# ARTIC_R2.net
KiCad netlist of a schematic drawn in EAGLE
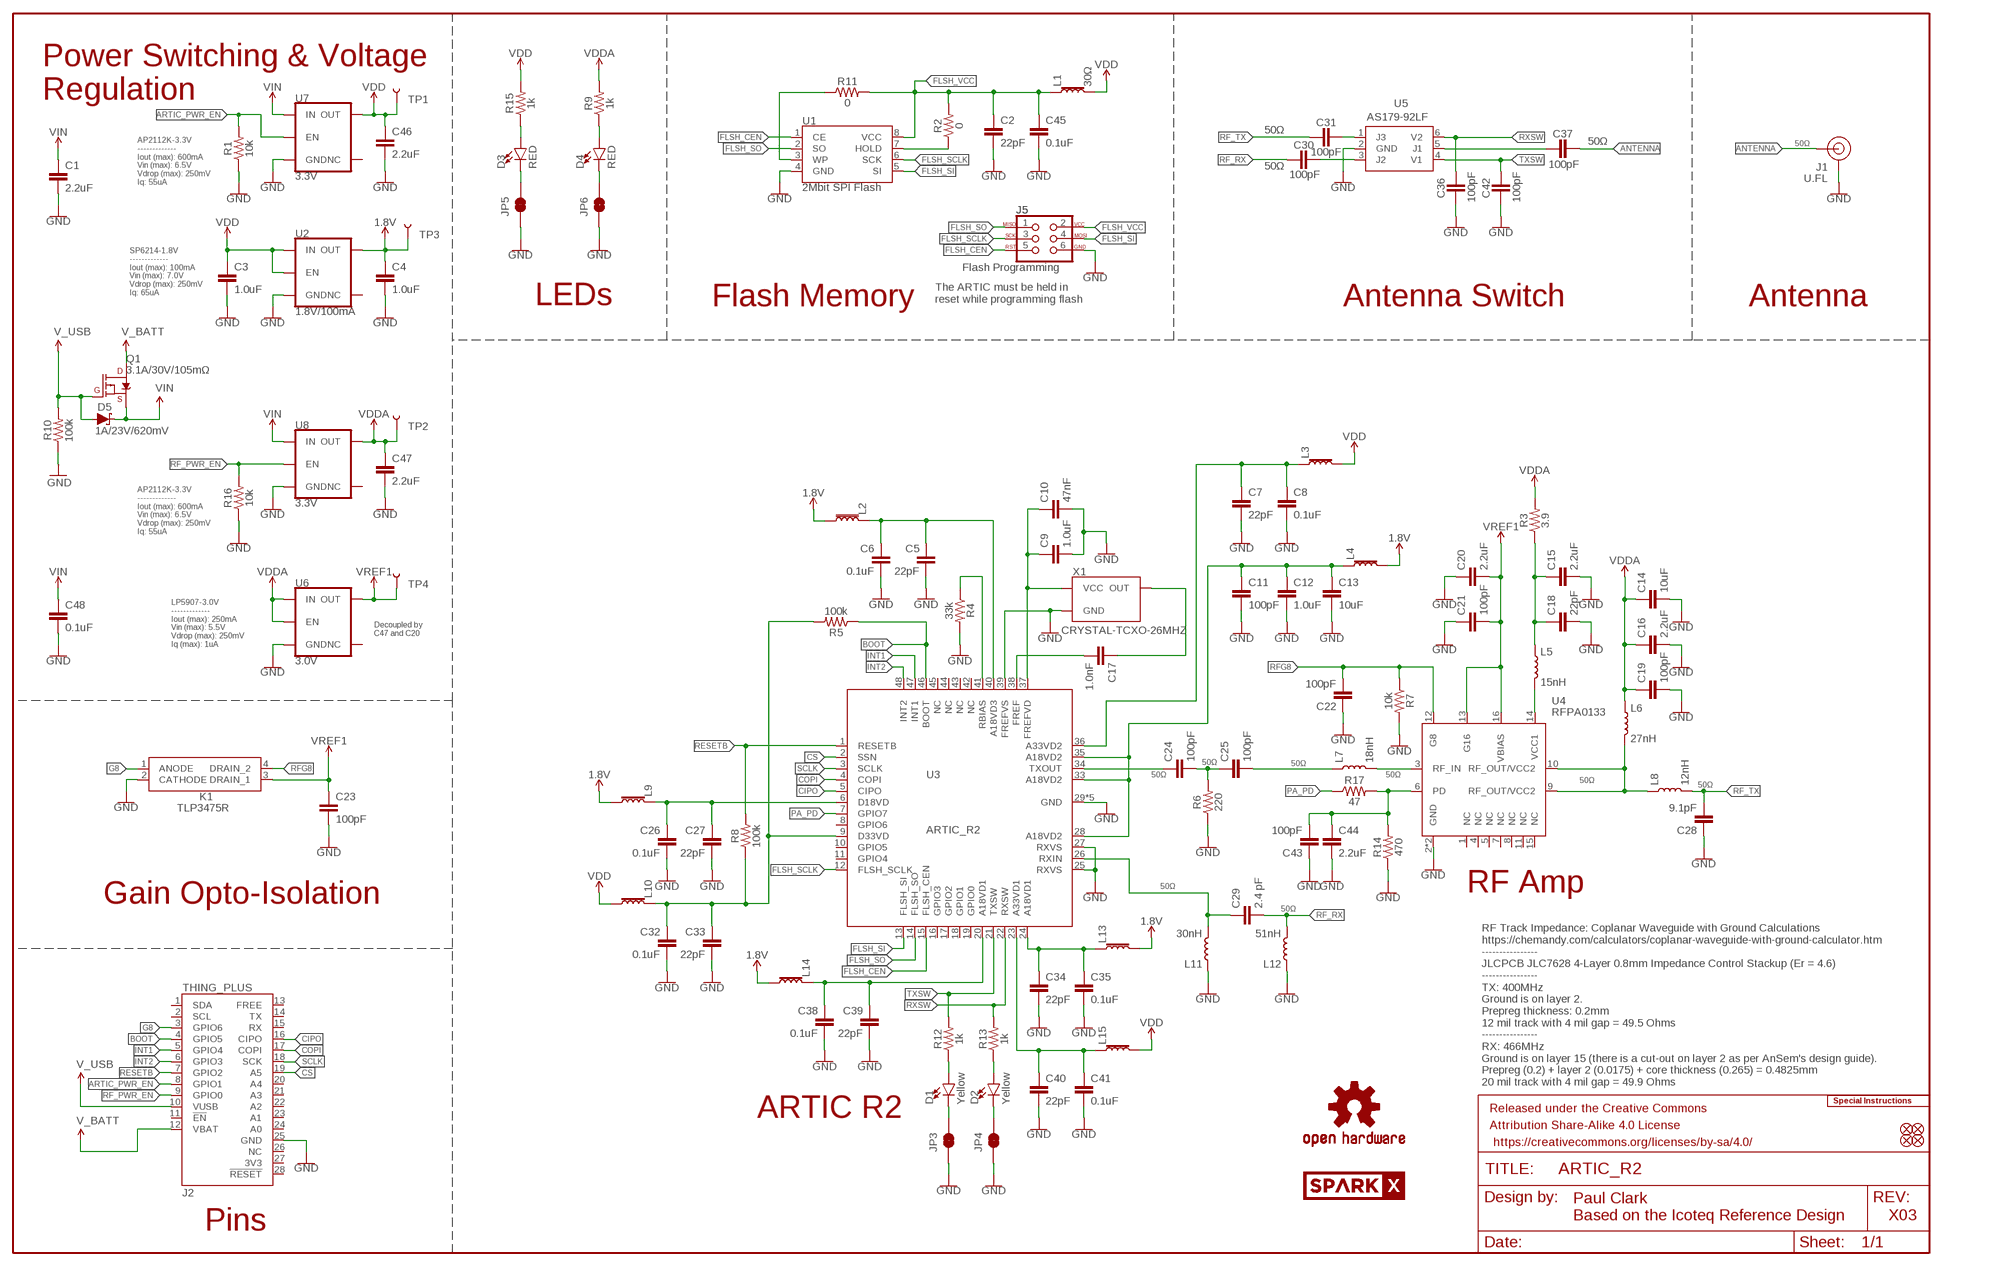
[diagram p0: schematic, sheet 1]

(export (version "E")
  (design (tool "Eeschema 10.0.6"))
  (components
    (comp (ref "C1")
      (value "2.2uF")
      (footprint "eagle-import:0402-TIGHT")
      (libsource (lib "eagle-import") (part "2.2UF-0402_TIGHT-10V-10%-X5R"))
    )
    (comp (ref "C2")
      (value "22pF")
      (footprint "eagle-import:0402-TIGHT")
      (libsource (lib "eagle-import") (part "22PF-0402T-16V-10%"))
    )
    (comp (ref "C3")
      (value "1.0uF")
      (footprint "eagle-import:0402-TIGHT")
      (libsource (lib "eagle-import") (part "1.0UF-0402T-16V-10%"))
    )
    (comp (ref "C4")
      (value "1.0uF")
      (footprint "eagle-import:0402-TIGHT")
      (libsource (lib "eagle-import") (part "1.0UF-0402T-16V-10%"))
    )
    (comp (ref "C5")
      (value "22pF")
      (footprint "eagle-import:0402-TIGHT")
      (libsource (lib "eagle-import") (part "22PF-0402T-16V-10%"))
    )
    (comp (ref "C6")
      (value "0.1uF")
      (footprint "eagle-import:0402-TIGHT")
      (libsource (lib "eagle-import") (part "0.1UF-0402T-6.3V-10%-X7R"))
    )
    (comp (ref "C7")
      (value "22pF")
      (footprint "eagle-import:0402-TIGHT")
      (libsource (lib "eagle-import") (part "22PF-0402T-16V-10%"))
    )
    (comp (ref "C8")
      (value "0.1uF")
      (footprint "eagle-import:0402-TIGHT")
      (libsource (lib "eagle-import") (part "0.1UF-0402T-6.3V-10%-X7R"))
    )
    (comp (ref "C9")
      (value "1.0uF")
      (footprint "eagle-import:0402-TIGHT")
      (libsource (lib "eagle-import") (part "1.0UF-0402T-16V-10%"))
    )
    (comp (ref "C10")
      (value "47nF")
      (footprint "eagle-import:0402-TIGHT")
      (libsource (lib "eagle-import") (part "47NF-0402_TIGHT-25V-10%-X7R"))
    )
    (comp (ref "C11")
      (value "100pF")
      (footprint "eagle-import:0402-TIGHT")
      (libsource (lib "eagle-import") (part "100PF-0402T-50V-5%"))
    )
    (comp (ref "C12")
      (value "1.0uF")
      (footprint "eagle-import:0402-TIGHT")
      (libsource (lib "eagle-import") (part "1.0UF-0402T-16V-10%"))
    )
    (comp (ref "C13")
      (value "10uF")
      (footprint "eagle-import:0402-TIGHT")
      (libsource (lib "eagle-import") (part "10UF-0402T-6.3V-20%"))
    )
    (comp (ref "C14")
      (value "10uF")
      (footprint "eagle-import:0402-TIGHT")
      (libsource (lib "eagle-import") (part "10UF-0402T-6.3V-20%"))
    )
    (comp (ref "C15")
      (value "2.2uF")
      (footprint "eagle-import:0402-TIGHT")
      (libsource (lib "eagle-import") (part "2.2UF-0402_TIGHT-10V-10%-X5R"))
    )
    (comp (ref "C16")
      (value "2.2uF")
      (footprint "eagle-import:0402-TIGHT")
      (libsource (lib "eagle-import") (part "2.2UF-0402_TIGHT-10V-10%-X5R"))
    )
    (comp (ref "C17")
      (value "1.0nF")
      (footprint "eagle-import:0402-TIGHT")
      (libsource (lib "eagle-import") (part "1.0NF/1000PF-0402_TIGHT-50V-10%"))
    )
    (comp (ref "C18")
      (value "22pF")
      (footprint "eagle-import:0402-TIGHT")
      (libsource (lib "eagle-import") (part "22PF-0402T-16V-10%"))
    )
    (comp (ref "C19")
      (value "100pF")
      (footprint "eagle-import:0402-TIGHT")
      (libsource (lib "eagle-import") (part "100PF-0402T-50V-5%"))
    )
    (comp (ref "C20")
      (value "2.2uF")
      (footprint "eagle-import:0402-TIGHT")
      (libsource (lib "eagle-import") (part "2.2UF-0402_TIGHT-10V-10%-X5R"))
    )
    (comp (ref "C21")
      (value "100pF")
      (footprint "eagle-import:0402-TIGHT")
      (libsource (lib "eagle-import") (part "100PF-0402T-50V-5%"))
    )
    (comp (ref "C22")
      (value "100pF")
      (footprint "eagle-import:0402-TIGHT")
      (libsource (lib "eagle-import") (part "100PF-0402T-50V-5%"))
    )
    (comp (ref "C23")
      (value "100pF")
      (footprint "eagle-import:0402-TIGHT")
      (libsource (lib "eagle-import") (part "100PF-0402T-50V-5%"))
    )
    (comp (ref "C24")
      (value "100pF")
      (footprint "eagle-import:0402-TIGHT")
      (libsource (lib "eagle-import") (part "100PF-0402T-50V-5%"))
    )
    (comp (ref "C25")
      (value "100pF")
      (footprint "eagle-import:0402-TIGHT")
      (libsource (lib "eagle-import") (part "100PF-0402T-50V-5%"))
    )
    (comp (ref "C26")
      (value "0.1uF")
      (footprint "eagle-import:0402-TIGHT")
      (libsource (lib "eagle-import") (part "0.1UF-0402T-6.3V-10%-X7R"))
    )
    (comp (ref "C27")
      (value "22pF")
      (footprint "eagle-import:0402-TIGHT")
      (libsource (lib "eagle-import") (part "22PF-0402T-16V-10%"))
    )
    (comp (ref "C28")
      (value "9.1pF")
      (footprint "eagle-import:0402-TIGHT")
      (fields (field (name "MOUSER_PART") "609-500R07S9R1CV4T"))
      (libsource (lib "eagle-import") (part "9.1PF-0402-TIGHT"))
    )
    (comp (ref "C29")
      (value "2.4 pF")
      (footprint "eagle-import:0402_MURATA")
      (libsource (lib "eagle-import") (part "2.4PF-0402"))
    )
    (comp (ref "C30")
      (value "100pF")
      (footprint "eagle-import:0402-TIGHT")
      (libsource (lib "eagle-import") (part "100PF-0402T-50V-5%"))
    )
    (comp (ref "C31")
      (value "100pF")
      (footprint "eagle-import:0402-TIGHT")
      (libsource (lib "eagle-import") (part "100PF-0402T-50V-5%"))
    )
    (comp (ref "C32")
      (value "0.1uF")
      (footprint "eagle-import:0402-TIGHT")
      (libsource (lib "eagle-import") (part "0.1UF-0402T-6.3V-10%-X7R"))
    )
    (comp (ref "C33")
      (value "22pF")
      (footprint "eagle-import:0402-TIGHT")
      (libsource (lib "eagle-import") (part "22PF-0402T-16V-10%"))
    )
    (comp (ref "C34")
      (value "22pF")
      (footprint "eagle-import:0402-TIGHT")
      (libsource (lib "eagle-import") (part "22PF-0402T-16V-10%"))
    )
    (comp (ref "C35")
      (value "0.1uF")
      (footprint "eagle-import:0402-TIGHT")
      (libsource (lib "eagle-import") (part "0.1UF-0402T-6.3V-10%-X7R"))
    )
    (comp (ref "C36")
      (value "100pF")
      (footprint "eagle-import:0402-TIGHT")
      (libsource (lib "eagle-import") (part "100PF-0402T-50V-5%"))
    )
    (comp (ref "C37")
      (value "100pF")
      (footprint "eagle-import:0402-TIGHT")
      (libsource (lib "eagle-import") (part "100PF-0402T-50V-5%"))
    )
    (comp (ref "C38")
      (value "0.1uF")
      (footprint "eagle-import:0402-TIGHT")
      (libsource (lib "eagle-import") (part "0.1UF-0402T-6.3V-10%-X7R"))
    )
    (comp (ref "C39")
      (value "22pF")
      (footprint "eagle-import:0402-TIGHT")
      (libsource (lib "eagle-import") (part "22PF-0402T-16V-10%"))
    )
    (comp (ref "C40")
      (value "22pF")
      (footprint "eagle-import:0402-TIGHT")
      (libsource (lib "eagle-import") (part "22PF-0402T-16V-10%"))
    )
    (comp (ref "C41")
      (value "0.1uF")
      (footprint "eagle-import:0402-TIGHT")
      (libsource (lib "eagle-import") (part "0.1UF-0402T-6.3V-10%-X7R"))
    )
    (comp (ref "C42")
      (value "100pF")
      (footprint "eagle-import:0402-TIGHT")
      (libsource (lib "eagle-import") (part "100PF-0402T-50V-5%"))
    )
    (comp (ref "C43")
      (value "100pF")
      (footprint "eagle-import:0402-TIGHT")
      (libsource (lib "eagle-import") (part "100PF-0402T-50V-5%"))
    )
    (comp (ref "C44")
      (value "2.2uF")
      (footprint "eagle-import:0402-TIGHT")
      (libsource (lib "eagle-import") (part "2.2UF-0402_TIGHT-10V-10%-X5R"))
    )
    (comp (ref "C45")
      (value "0.1uF")
      (footprint "eagle-import:0402-TIGHT")
      (libsource (lib "eagle-import") (part "0.1UF-0402T-6.3V-10%-X7R"))
    )
    (comp (ref "C46")
      (value "2.2uF")
      (footprint "eagle-import:0402-TIGHT")
      (libsource (lib "eagle-import") (part "2.2UF-0402_TIGHT-10V-10%-X5R"))
    )
    (comp (ref "C47")
      (value "2.2uF")
      (footprint "eagle-import:0402-TIGHT")
      (libsource (lib "eagle-import") (part "2.2UF-0402_TIGHT-10V-10%-X5R"))
    )
    (comp (ref "C48")
      (value "0.1uF")
      (footprint "eagle-import:0402-TIGHT")
      (libsource (lib "eagle-import") (part "0.1UF-0402T-10V-10%-X7R"))
    )
    (comp (ref "D1")
      (value "Yellow")
      (footprint "eagle-import:LED-0603")
      (libsource (lib "eagle-import") (part "LED-YELLOW0603"))
    )
    (comp (ref "D2")
      (value "Yellow")
      (footprint "eagle-import:LED-0603")
      (libsource (lib "eagle-import") (part "LED-YELLOW0603"))
    )
    (comp (ref "D3")
      (value "RED")
      (footprint "eagle-import:LED-0603")
      (libsource (lib "eagle-import") (part "LED-RED0603"))
    )
    (comp (ref "D4")
      (value "RED")
      (footprint "eagle-import:LED-0603")
      (libsource (lib "eagle-import") (part "LED-RED0603"))
    )
    (comp (ref "D5")
      (value "1A/23V/620mV")
      (footprint "eagle-import:SOD-323")
      (libsource (lib "eagle-import") (part "DIODE-SCHOTTKY-BAT20J"))
    )
    (comp (ref "FD1")
      (value "FIDUCIAL1X2")
      (footprint "eagle-import:FIDUCIAL-1X2")
      (libsource (lib "eagle-import") (part "FIDUCIAL1X2"))
    )
    (comp (ref "FD2")
      (value "FIDUCIAL1X2")
      (footprint "eagle-import:FIDUCIAL-1X2")
      (libsource (lib "eagle-import") (part "FIDUCIAL1X2"))
    )
    (comp (ref "FD3")
      (value "FIDUCIAL1X2")
      (footprint "eagle-import:FIDUCIAL-1X2")
      (libsource (lib "eagle-import") (part "FIDUCIAL1X2"))
    )
    (comp (ref "FD4")
      (value "FIDUCIAL1X2")
      (footprint "eagle-import:FIDUCIAL-1X2")
      (libsource (lib "eagle-import") (part "FIDUCIAL1X2"))
    )
    (comp (ref "FRAME1")
      (value "FRAME-LEDGER")
      (footprint "eagle-import:CREATIVE_COMMONS")
      (libsource (lib "eagle-import") (part "FRAME-LEDGER"))
    )
    (comp (ref "J1")
      (value "U.FL")
      (footprint "eagle-import:U.FL")
      (libsource (lib "eagle-import") (part "U.FL2PIN"))
    )
    (comp (ref "J2")
      (value "THING_PLUS")
      (footprint "eagle-import:THING_PLUS")
      (libsource (lib "eagle-import") (part "THING_PLUS"))
    )
    (comp (ref "J5")
      (value "Flash Programming")
      (footprint "eagle-import:2X3_TEST_POINTS")
      (libsource (lib "eagle-import") (part "AVR_SPI_PROG_3X2TESTPOINTS"))
    )
    (comp (ref "JP3")
      (value "JUMPER-SMT_2_NC_TRACE_SILK")
      (footprint "eagle-import:SMT-JUMPER_2_NC_TRACE_SILK")
      (libsource (lib "eagle-import") (part "JUMPER-SMT_2_NC_TRACE_SILK"))
    )
    (comp (ref "JP4")
      (value "JUMPER-SMT_2_NC_TRACE_SILK")
      (footprint "eagle-import:SMT-JUMPER_2_NC_TRACE_SILK")
      (libsource (lib "eagle-import") (part "JUMPER-SMT_2_NC_TRACE_SILK"))
    )
    (comp (ref "JP5")
      (value "JUMPER-SMT_2_NC_TRACE_SILK")
      (footprint "eagle-import:SMT-JUMPER_2_NC_TRACE_SILK")
      (libsource (lib "eagle-import") (part "JUMPER-SMT_2_NC_TRACE_SILK"))
    )
    (comp (ref "JP6")
      (value "JUMPER-SMT_2_NC_TRACE_SILK")
      (footprint "eagle-import:SMT-JUMPER_2_NC_TRACE_SILK")
      (libsource (lib "eagle-import") (part "JUMPER-SMT_2_NC_TRACE_SILK"))
    )
    (comp (ref "K1")
      (value "TLP3475R")
      (footprint "eagle-import:TLP3475RTPF")
      (fields (field (name "DIGIKEY_PART") "TLP3475R(TPFCT-ND - Cut Tape (CT)"))
      (libsource (lib "eagle-import") (part "TLP3475R"))
    )
    (comp (ref "L1")
      (value "30Ω")
      (footprint "eagle-import:0402-TIGHT")
      (libsource (lib "eagle-import") (part "FERRITE_BEAD-0402-30OHM-100MHZ"))
    )
    (comp (ref "L2")
      (value "30Ω")
      (footprint "eagle-import:0402-TIGHT")
      (libsource (lib "eagle-import") (part "FERRITE_BEAD-0402-30OHM-100MHZ"))
    )
    (comp (ref "L3")
      (value "30Ω")
      (footprint "eagle-import:0402-TIGHT")
      (libsource (lib "eagle-import") (part "FERRITE_BEAD-0402-30OHM-100MHZ"))
    )
    (comp (ref "L4")
      (value "30Ω")
      (footprint "eagle-import:0402-TIGHT")
      (libsource (lib "eagle-import") (part "FERRITE_BEAD-0402-30OHM-100MHZ"))
    )
    (comp (ref "L5")
      (value "15nH")
      (footprint "eagle-import:0402_COILCRAFT")
      (fields (field (name "MOUSER_PART") "994-0402HP-15NXGLU"))
      (libsource (lib "eagle-import") (part "15NH-0402"))
    )
    (comp (ref "L6")
      (value "27nH")
      (footprint "eagle-import:0402_COILCRAFT")
      (fields (field (name "MOUSER_PART") "994-0402HP-27NXGLU"))
      (libsource (lib "eagle-import") (part "27NH-0402"))
    )
    (comp (ref "L7")
      (value "18nH")
      (footprint "eagle-import:0402_COILCRAFT")
      (fields (field (name "MOUSER_PART") "994-0402HP-18NXGLU"))
      (libsource (lib "eagle-import") (part "18NH-0402"))
    )
    (comp (ref "L8")
      (value "12nH")
      (footprint "eagle-import:0402_COILCRAFT")
      (fields (field (name "MOUSER_PART") "994-0402HP-12NXGLU"))
      (libsource (lib "eagle-import") (part "12NH-0402"))
    )
    (comp (ref "L9")
      (value "30Ω")
      (footprint "eagle-import:0402-TIGHT")
      (libsource (lib "eagle-import") (part "FERRITE_BEAD-0402-30OHM-100MHZ"))
    )
    (comp (ref "L10")
      (value "30Ω")
      (footprint "eagle-import:0402-TIGHT")
      (libsource (lib "eagle-import") (part "FERRITE_BEAD-0402-30OHM-100MHZ"))
    )
    (comp (ref "L11")
      (value "30nH")
      (footprint "eagle-import:0402_COILCRAFT")
      (fields (field (name "MOUSER_PART") "994-0402HP-30NXGLU"))
      (libsource (lib "eagle-import") (part "30NH-0402"))
    )
    (comp (ref "L12")
      (value "51nH")
      (footprint "eagle-import:0402_COILCRAFT")
      (fields (field (name "MOUSER_PART") "994-0402HP-51NXGLU"))
      (libsource (lib "eagle-import") (part "51NH-0402"))
    )
    (comp (ref "L13")
      (value "30Ω")
      (footprint "eagle-import:0402-TIGHT")
      (libsource (lib "eagle-import") (part "FERRITE_BEAD-0402-30OHM-100MHZ"))
    )
    (comp (ref "L14")
      (value "30Ω")
      (footprint "eagle-import:0402-TIGHT")
      (libsource (lib "eagle-import") (part "FERRITE_BEAD-0402-30OHM-100MHZ"))
    )
    (comp (ref "L15")
      (value "30Ω")
      (footprint "eagle-import:0402-TIGHT")
      (libsource (lib "eagle-import") (part "FERRITE_BEAD-0402-30OHM-100MHZ"))
    )
    (comp (ref "LOGO1")
      (value "SPECIAL_INSTRUCTIONS-ORDERING")
      (footprint "eagle-import:ORDERING_INSTRUCTIONS")
      (libsource (lib "eagle-import") (part "SPECIAL_INSTRUCTIONS-ORDERING"))
    )
    (comp (ref "LOGO2")
      (value "OSHW-LOGOS")
      (footprint "eagle-import:OSHW-LOGO-S")
      (libsource (lib "eagle-import") (part "OSHW-LOGOS"))
    )
    (comp (ref "LOGO3")
      (value "OSHW-LOGOS")
      (footprint "eagle-import:OSHW-LOGO-S")
      (libsource (lib "eagle-import") (part "OSHW-LOGOS"))
    )
    (comp (ref "Q1")
      (value "3.1A/30V/105mΩ")
      (footprint "eagle-import:SOT23-3")
      (libsource (lib "eagle-import") (part "MOSFET_PCH-DMG2307L"))
    )
    (comp (ref "R1")
      (value "10k")
      (footprint "eagle-import:0402-TIGHT")
      (libsource (lib "eagle-import") (part "10KOHM-0402T-1/16W-1%"))
    )
    (comp (ref "R2")
      (value "0")
      (footprint "eagle-import:0402-TIGHT")
      (libsource (lib "eagle-import") (part "0OHM-0402T-1/10W"))
    )
    (comp (ref "R3")
      (value "3.9")
      (footprint "eagle-import:0402-TIGHT")
      (libsource (lib "eagle-import") (part "3.9OHM-0402-TIGHT-1/16W-1%"))
    )
    (comp (ref "R4")
      (value "33k")
      (footprint "eagle-import:0402-TIGHT")
      (libsource (lib "eagle-import") (part "33KOHM-0402T-1/16W-1%"))
    )
    (comp (ref "R5")
      (value "100k")
      (footprint "eagle-import:0402-TIGHT")
      (libsource (lib "eagle-import") (part "100KOHM-0402T-1/16W-1%"))
    )
    (comp (ref "R6")
      (value "220")
      (footprint "eagle-import:0402-TIGHT")
      (libsource (lib "eagle-import") (part "220OHM-0402-TIGHT-1/16W-1%"))
    )
    (comp (ref "R7")
      (value "10k")
      (footprint "eagle-import:0402-TIGHT")
      (libsource (lib "eagle-import") (part "10KOHM-0402T-1/16W-1%"))
    )
    (comp (ref "R8")
      (value "100k")
      (footprint "eagle-import:0402-TIGHT")
      (libsource (lib "eagle-import") (part "100KOHM-0402T-1/16W-1%"))
    )
    (comp (ref "R9")
      (value "1k")
      (footprint "eagle-import:0402-TIGHT")
      (libsource (lib "eagle-import") (part "1KOHM-0402T-1/16W-1%"))
    )
    (comp (ref "R10")
      (value "100k")
      (footprint "eagle-import:0402-TIGHT")
      (libsource (lib "eagle-import") (part "100KOHM-0402T-1/16W-1%"))
    )
    (comp (ref "R11")
      (value "0")
      (footprint "eagle-import:0402-TIGHT")
      (libsource (lib "eagle-import") (part "0OHM-0402T-1/10W"))
    )
    (comp (ref "R12")
      (value "1k")
      (footprint "eagle-import:0402-TIGHT")
      (libsource (lib "eagle-import") (part "1KOHM-0402T-1/16W-1%"))
    )
    (comp (ref "R13")
      (value "1k")
      (footprint "eagle-import:0402-TIGHT")
      (libsource (lib "eagle-import") (part "1KOHM-0402T-1/16W-1%"))
    )
    (comp (ref "R14")
      (value "470")
      (footprint "eagle-import:0402-TIGHT")
      (libsource (lib "eagle-import") (part "470OHM-0402-TIGHT-1/16W-1%"))
    )
    (comp (ref "R15")
      (value "1k")
      (footprint "eagle-import:0402-TIGHT")
      (libsource (lib "eagle-import") (part "1KOHM-0402T-1/16W-1%"))
    )
    (comp (ref "R16")
      (value "10k")
      (footprint "eagle-import:0402-TIGHT")
      (libsource (lib "eagle-import") (part "10KOHM-0402T-1/16W-1%"))
    )
    (comp (ref "R17")
      (value "47")
      (footprint "eagle-import:0402-TIGHT")
      (libsource (lib "eagle-import") (part "47OHM-0402-TIGHT-1/16W-1%"))
    )
    (comp (ref "SPARKX1")
      (value "SPARKX-LOGO4")
      (footprint "eagle-import:SPARKX-MEDIUM")
      (libsource (lib "eagle-import") (part "SPARKX-LOGO4"))
    )
    (comp (ref "SPARKX2")
      (value "SPARKX-LOGO4")
      (footprint "eagle-import:SPARKX-MEDIUM")
      (libsource (lib "eagle-import") (part "SPARKX-LOGO4"))
    )
    (comp (ref "TP1")
      (value "TEST-POINTTP_15TH_THRU")
      (footprint "eagle-import:TP_15TH")
      (libsource (lib "eagle-import") (part "TEST-POINTTP_15TH_THRU"))
    )
    (comp (ref "TP2")
      (value "TEST-POINTTP_15TH_THRU")
      (footprint "eagle-import:TP_15TH")
      (libsource (lib "eagle-import") (part "TEST-POINTTP_15TH_THRU"))
    )
    (comp (ref "TP3")
      (value "TEST-POINTTP_15TH_THRU")
      (footprint "eagle-import:TP_15TH")
      (libsource (lib "eagle-import") (part "TEST-POINTTP_15TH_THRU"))
    )
    (comp (ref "TP4")
      (value "TEST-POINTTP_15TH_THRU")
      (footprint "eagle-import:TP_15TH")
      (libsource (lib "eagle-import") (part "TEST-POINTTP_15TH_THRU"))
    )
    (comp (ref "U1")
      (value "2Mbit SPI Flash")
      (footprint "eagle-import:SO08")
      (fields
        (field (name "DIGIKEY_PART") " SST25VF020B-80-4I-SAE-TCT-ND")
        (field (name "MANUFACTURER") "Microchip")
        (field (name "MANU_PART") "SST25VF020B-80-4I-SAE-T")
      )
      (libsource (lib "eagle-import") (part "SST25VF020BSO08_INDUSTRIAL_TEMP"))
    )
    (comp (ref "U2")
      (value "1.8V/100mA")
      (footprint "eagle-import:SC70")
      (libsource (lib "eagle-import") (part "V_REG_SP6214-1.8V"))
    )
    (comp (ref "U3")
      (value "ARTIC_R2")
      (footprint "eagle-import:QFN-48")
      (libsource (lib "eagle-import") (part "ARTIC_R2"))
    )
    (comp (ref "U4")
      (value "RFPA0133")
      (footprint "eagle-import:QFN50P300X300X86-17N")
      (fields
        (field (name "MANUFACTURER_PART_NUMBER") "RFPA0133TR7")
        (field (name "MOUSER_PART_NUMBER") "772-RFPA0133")
      )
      (libsource (lib "eagle-import") (part "RFPA0133"))
    )
    (comp (ref "U5")
      (value "AS179-92LF")
      (footprint "eagle-import:SOT65P220X100-6N")
      (libsource (lib "eagle-import") (part "AS179-92LF"))
    )
    (comp (ref "U6")
      (value "3.0V")
      (footprint "eagle-import:SOT23-5")
      (fields
        (field (name "DIGIKEY_PART") "296-40357-1-ND")
        (field (name "MANU_PART") "LP5907MFX-3.0/NOPB")
        (field (name "MOUSER_PART") "595-LP5907MFX-3.0NPB")
      )
      (libsource (lib "eagle-import") (part "V_REG_LP5907SOT23-3.0V"))
    )
    (comp (ref "U7")
      (value "3.3V")
      (footprint "eagle-import:SOT23-5")
      (libsource (lib "eagle-import") (part "V_REG_AP2112K-3.3V"))
    )
    (comp (ref "U8")
      (value "3.3V")
      (footprint "eagle-import:SOT23-5")
      (libsource (lib "eagle-import") (part "V_REG_AP2112K-3.3V"))
    )
    (comp (ref "X1")
      (value "CRYSTAL-TCXO-26MHZ")
      (footprint "eagle-import:CRYSTAL-TCXO-SMD-1.65X1.25")
      (fields (field (name "MOUSER_PART") "449-LFTCXO073004CUTT"))
      (libsource (lib "eagle-import") (part "CRYSTAL-TCXO-26MHZ"))
    )
  )
  (nets
    (net (code "1") (name "1.8V") (class "Default")
      (node (ref "C4") (pin "1") (pinfunction "1_1") (pintype "passive"))
      (node (ref "L13") (pin "2") (pinfunction "2_2") (pintype "passive"))
      (node (ref "L14") (pin "2") (pinfunction "2_2") (pintype "passive"))
      (node (ref "L2") (pin "2") (pinfunction "2_2") (pintype "passive"))
      (node (ref "L4") (pin "2") (pinfunction "2_2") (pintype "passive"))
      (node (ref "L9") (pin "2") (pinfunction "2_2") (pintype "passive"))
      (node (ref "TP3") (pin "P$1") (pinfunction "1_P$1") (pintype "bidirectional"))
      (node (ref "U2") (pin "5") (pinfunction "OUT_5") (pintype "passive"))
    )
    (net (code "2") (name "ANTENNA") (class "Default")
      (node (ref "C37") (pin "1") (pinfunction "1_1") (pintype "passive"))
      (node (ref "J1") (pin "FEED") (pinfunction "SIGNAL_FEED") (pintype "bidirectional"))
    )
    (net (code "3") (name "ARTIC_PWR_EN") (class "Default")
      (node (ref "J2") (pin "8") (pinfunction "GPIO1_8") (pintype "bidirectional"))
      (node (ref "R1") (pin "2") (pinfunction "2_2") (pintype "passive"))
      (node (ref "U7") (pin "3") (pinfunction "EN_3") (pintype "input"))
    )
    (net (code "4") (name "BOOT") (class "Default")
      (node (ref "J2") (pin "4") (pinfunction "GPIO5_4") (pintype "bidirectional"))
      (node (ref "R5") (pin "1") (pinfunction "1_1") (pintype "passive"))
      (node (ref "U3") (pin "46") (pinfunction "BOOT_46") (pintype "bidirectional"))
    )
    (net (code "5") (name "CIPO") (class "Default")
      (node (ref "J2") (pin "16") (pinfunction "CIPO_16") (pintype "bidirectional"))
      (node (ref "U3") (pin "5") (pinfunction "CIPO_5") (pintype "bidirectional"))
    )
    (net (code "6") (name "COPI") (class "Default")
      (node (ref "J2") (pin "17") (pinfunction "COPI_17") (pintype "bidirectional"))
      (node (ref "U3") (pin "4") (pinfunction "COPI_4") (pintype "bidirectional"))
    )
    (net (code "7") (name "CS") (class "Default")
      (node (ref "J2") (pin "19") (pinfunction "A5_19") (pintype "bidirectional"))
      (node (ref "U3") (pin "2") (pinfunction "SSN_2") (pintype "bidirectional"))
    )
    (net (code "8") (name "FLSH_CEN") (class "Default")
      (node (ref "J5") (pin "5") (pinfunction "5_5") (pintype "passive"))
      (node (ref "U1") (pin "1") (pinfunction "CE_1") (pintype "bidirectional"))
      (node (ref "U3") (pin "15") (pinfunction "FLSH_CEN_15") (pintype "bidirectional"))
    )
    (net (code "9") (name "FLSH_SCLK") (class "Default")
      (node (ref "J5") (pin "3") (pinfunction "3_3") (pintype "passive"))
      (node (ref "U1") (pin "6") (pinfunction "SCK_6") (pintype "bidirectional"))
      (node (ref "U3") (pin "12") (pinfunction "FLSH_SCLK_12") (pintype "bidirectional"))
    )
    (net (code "10") (name "FLSH_SI") (class "Default")
      (node (ref "J5") (pin "4") (pinfunction "4_4") (pintype "passive"))
      (node (ref "U1") (pin "5") (pinfunction "SI_5") (pintype "bidirectional"))
      (node (ref "U3") (pin "13") (pinfunction "FLSH_SI_13") (pintype "bidirectional"))
    )
    (net (code "11") (name "FLSH_SO") (class "Default")
      (node (ref "J5") (pin "1") (pinfunction "1_1") (pintype "passive"))
      (node (ref "U1") (pin "2") (pinfunction "SO_2") (pintype "bidirectional"))
      (node (ref "U3") (pin "14") (pinfunction "FLSH_SO_14") (pintype "bidirectional"))
    )
    (net (code "12") (name "FLSH_VCC") (class "Default")
      (node (ref "C2") (pin "1") (pinfunction "1_1") (pintype "passive"))
      (node (ref "C45") (pin "1") (pinfunction "1_1") (pintype "passive"))
      (node (ref "J5") (pin "2") (pinfunction "2_2") (pintype "passive"))
      (node (ref "L1") (pin "1") (pinfunction "1_1") (pintype "passive"))
      (node (ref "R11") (pin "2") (pinfunction "2_2") (pintype "passive"))
      (node (ref "R2") (pin "2") (pinfunction "2_2") (pintype "passive"))
      (node (ref "U1") (pin "8") (pinfunction "VCC_8") (pintype "power_in"))
    )
    (net (code "13") (name "G8") (class "Default")
      (node (ref "J2") (pin "3") (pinfunction "GPIO6_3") (pintype "bidirectional"))
      (node (ref "K1") (pin "1") (pinfunction "ANODE_1") (pintype "bidirectional"))
    )
    (net (code "14") (name "GND") (class "Default")
      (node (ref "C1") (pin "2") (pinfunction "2_2") (pintype "passive"))
      (node (ref "C10") (pin "2") (pinfunction "2_2") (pintype "passive"))
      (node (ref "C11") (pin "2") (pinfunction "2_2") (pintype "passive"))
      (node (ref "C12") (pin "2") (pinfunction "2_2") (pintype "passive"))
      (node (ref "C13") (pin "2") (pinfunction "2_2") (pintype "passive"))
      (node (ref "C14") (pin "2") (pinfunction "2_2") (pintype "passive"))
      (node (ref "C15") (pin "2") (pinfunction "2_2") (pintype "passive"))
      (node (ref "C16") (pin "2") (pinfunction "2_2") (pintype "passive"))
      (node (ref "C18") (pin "2") (pinfunction "2_2") (pintype "passive"))
      (node (ref "C19") (pin "2") (pinfunction "2_2") (pintype "passive"))
      (node (ref "C2") (pin "2") (pinfunction "2_2") (pintype "passive"))
      (node (ref "C20") (pin "1") (pinfunction "1_1") (pintype "passive"))
      (node (ref "C21") (pin "1") (pinfunction "1_1") (pintype "passive"))
      (node (ref "C22") (pin "1") (pinfunction "1_1") (pintype "passive"))
      (node (ref "C23") (pin "2") (pinfunction "2_2") (pintype "passive"))
      (node (ref "C26") (pin "2") (pinfunction "2_2") (pintype "passive"))
      (node (ref "C27") (pin "2") (pinfunction "2_2") (pintype "passive"))
      (node (ref "C28") (pin "1") (pinfunction "1_1") (pintype "passive"))
      (node (ref "C3") (pin "2") (pinfunction "2_2") (pintype "passive"))
      (node (ref "C32") (pin "2") (pinfunction "2_2") (pintype "passive"))
      (node (ref "C33") (pin "2") (pinfunction "2_2") (pintype "passive"))
      (node (ref "C34") (pin "2") (pinfunction "2_2") (pintype "passive"))
      (node (ref "C35") (pin "2") (pinfunction "2_2") (pintype "passive"))
      (node (ref "C36") (pin "2") (pinfunction "2_2") (pintype "passive"))
      (node (ref "C38") (pin "2") (pinfunction "2_2") (pintype "passive"))
      (node (ref "C39") (pin "2") (pinfunction "2_2") (pintype "passive"))
      (node (ref "C4") (pin "2") (pinfunction "2_2") (pintype "passive"))
      (node (ref "C40") (pin "2") (pinfunction "2_2") (pintype "passive"))
      (node (ref "C41") (pin "2") (pinfunction "2_2") (pintype "passive"))
      (node (ref "C42") (pin "2") (pinfunction "2_2") (pintype "passive"))
      (node (ref "C43") (pin "1") (pinfunction "1_1") (pintype "passive"))
      (node (ref "C44") (pin "2") (pinfunction "2_2") (pintype "passive"))
      (node (ref "C45") (pin "2") (pinfunction "2_2") (pintype "passive"))
      (node (ref "C46") (pin "2") (pinfunction "2_2") (pintype "passive"))
      (node (ref "C47") (pin "2") (pinfunction "2_2") (pintype "passive"))
      (node (ref "C48") (pin "2") (pinfunction "2_2") (pintype "passive"))
      (node (ref "C5") (pin "2") (pinfunction "2_2") (pintype "passive"))
      (node (ref "C6") (pin "2") (pinfunction "2_2") (pintype "passive"))
      (node (ref "C7") (pin "2") (pinfunction "2_2") (pintype "passive"))
      (node (ref "C8") (pin "2") (pinfunction "2_2") (pintype "passive"))
      (node (ref "C9") (pin "2") (pinfunction "2_2") (pintype "passive"))
      (node (ref "J1") (pin "1") (pinfunction "GND_1") (pintype "bidirectional"))
      (node (ref "J1") (pin "2") (pinfunction "GND_2") (pintype "bidirectional"))
      (node (ref "J2") (pin "25") (pinfunction "GND_25") (pintype "bidirectional"))
      (node (ref "J5") (pin "6") (pinfunction "6_6") (pintype "passive"))
      (node (ref "JP3") (pin "1") (pinfunction "1_1") (pintype "passive"))
      (node (ref "JP4") (pin "1") (pinfunction "1_1") (pintype "passive"))
      (node (ref "JP5") (pin "1") (pinfunction "1_1") (pintype "passive"))
      (node (ref "JP6") (pin "1") (pinfunction "1_1") (pintype "passive"))
      (node (ref "K1") (pin "2") (pinfunction "CATHODE_2") (pintype "bidirectional"))
      (node (ref "L11") (pin "P$1") (pinfunction "1_P$1") (pintype "passive"))
      (node (ref "L12") (pin "P$1") (pinfunction "1_P$1") (pintype "passive"))
      (node (ref "R1") (pin "1") (pinfunction "1_1") (pintype "passive"))
      (node (ref "R10") (pin "1") (pinfunction "1_1") (pintype "passive"))
      (node (ref "R14") (pin "1") (pinfunction "1_1") (pintype "passive"))
      (node (ref "R16") (pin "1") (pinfunction "1_1") (pintype "passive"))
      (node (ref "R4") (pin "2") (pinfunction "2_2") (pintype "passive"))
      (node (ref "R6") (pin "1") (pinfunction "1_1") (pintype "passive"))
      (node (ref "R7") (pin "2") (pinfunction "2_2") (pintype "passive"))
      (node (ref "U1") (pin "4") (pinfunction "GND_4") (pintype "power_in"))
      (node (ref "U2") (pin "2") (pinfunction "GND_2") (pintype "input"))
      (node (ref "U3") (pin "25") (pinfunction "RXVS_25") (pintype "bidirectional"))
      (node (ref "U3") (pin "27") (pinfunction "RXVS_27") (pintype "bidirectional"))
      (node (ref "U3") (pin "29") (pinfunction "GND_29") (pintype "bidirectional"))
      (node (ref "U3") (pin "30") (pinfunction "GND_30") (pintype "bidirectional"))
      (node (ref "U3") (pin "31") (pinfunction "GND_31") (pintype "bidirectional"))
      (node (ref "U3") (pin "32") (pinfunction "GND_32") (pintype "bidirectional"))
      (node (ref "U3") (pin "39") (pinfunction "FREFVS_39") (pintype "bidirectional"))
      (node (ref "U3") (pin "GND") (pinfunction "GND_GND") (pintype "bidirectional"))
      (node (ref "U4") (pin "2") (pinfunction "GND_2") (pintype "power_in"))
      (node (ref "U4") (pin "EDAP") (pinfunction "GND_EDAP") (pintype "power_in"))
      (node (ref "U5") (pin "2") (pinfunction "GND_2") (pintype "power_in"))
      (node (ref "U6") (pin "2") (pinfunction "GND_2") (pintype "input"))
      (node (ref "U7") (pin "2") (pinfunction "GND_2") (pintype "input"))
      (node (ref "U8") (pin "2") (pinfunction "GND_2") (pintype "input"))
      (node (ref "X1") (pin "1") (pinfunction "GND_1") (pintype "bidirectional"))
      (node (ref "X1") (pin "2") (pinfunction "GND_2") (pintype "bidirectional"))
    )
    (net (code "15") (name "INT1") (class "Default")
      (node (ref "J2") (pin "5") (pinfunction "GPIO4_5") (pintype "bidirectional"))
      (node (ref "U3") (pin "47") (pinfunction "INT1_47") (pintype "bidirectional"))
    )
    (net (code "16") (name "INT2") (class "Default")
      (node (ref "J2") (pin "6") (pinfunction "GPIO3_6") (pintype "bidirectional"))
      (node (ref "U3") (pin "48") (pinfunction "INT2_48") (pintype "bidirectional"))
    )
    (net (code "17") (name "Net-(C11-Pad1)") (class "Default")
      (node (ref "C11") (pin "1") (pinfunction "1_1") (pintype "passive"))
      (node (ref "C12") (pin "1") (pinfunction "1_1") (pintype "passive"))
      (node (ref "C13") (pin "1") (pinfunction "1_1") (pintype "passive"))
      (node (ref "L4") (pin "1") (pinfunction "1_1") (pintype "passive"))
      (node (ref "U3") (pin "28") (pinfunction "A18VD2_28") (pintype "power_in"))
      (node (ref "U3") (pin "33") (pinfunction "A18VD2_33") (pintype "power_in"))
      (node (ref "U3") (pin "35") (pinfunction "A18VD2_35") (pintype "power_in"))
    )
    (net (code "18") (name "Net-(C24-Pad2)") (class "Default")
      (node (ref "C24") (pin "2") (pinfunction "2_2") (pintype "passive"))
      (node (ref "C25") (pin "1") (pinfunction "1_1") (pintype "passive"))
      (node (ref "R6") (pin "2") (pinfunction "2_2") (pintype "passive"))
    )
    (net (code "19") (name "Net-(C29-1)") (class "Default")
      (node (ref "C29") (pin "P$1") (pinfunction "1_P$1") (pintype "passive"))
      (node (ref "L11") (pin "P$2") (pinfunction "2_P$2") (pintype "passive"))
      (node (ref "U3") (pin "26") (pinfunction "RXIN_26") (pintype "bidirectional"))
    )
    (net (code "20") (name "Net-(C34-Pad1)") (class "Default")
      (node (ref "C34") (pin "1") (pinfunction "1_1") (pintype "passive"))
      (node (ref "C35") (pin "1") (pinfunction "1_1") (pintype "passive"))
      (node (ref "L13") (pin "1") (pinfunction "1_1") (pintype "passive"))
      (node (ref "U3") (pin "24") (pinfunction "A18VD1_24") (pintype "power_in"))
    )
    (net (code "21") (name "Net-(C38-Pad1)") (class "Default")
      (node (ref "C38") (pin "1") (pinfunction "1_1") (pintype "passive"))
      (node (ref "C39") (pin "1") (pinfunction "1_1") (pintype "passive"))
      (node (ref "L14") (pin "1") (pinfunction "1_1") (pintype "passive"))
      (node (ref "U3") (pin "20") (pinfunction "A18VD1_20") (pintype "power_in"))
    )
    (net (code "22") (name "Net-(D1-PadA)") (class "Default")
      (node (ref "D1") (pin "A") (pinfunction "A_A") (pintype "passive"))
      (node (ref "R12") (pin "1") (pinfunction "1_1") (pintype "passive"))
    )
    (net (code "23") (name "Net-(D1-PadC)") (class "Default")
      (node (ref "D1") (pin "C") (pinfunction "C_C") (pintype "passive"))
      (node (ref "JP3") (pin "2") (pinfunction "2_2") (pintype "passive"))
    )
    (net (code "24") (name "Net-(D2-PadA)") (class "Default")
      (node (ref "D2") (pin "A") (pinfunction "A_A") (pintype "passive"))
      (node (ref "R13") (pin "1") (pinfunction "1_1") (pintype "passive"))
    )
    (net (code "25") (name "Net-(D2-PadC)") (class "Default")
      (node (ref "D2") (pin "C") (pinfunction "C_C") (pintype "passive"))
      (node (ref "JP4") (pin "2") (pinfunction "2_2") (pintype "passive"))
    )
    (net (code "26") (name "Net-(D3-PadA)") (class "Default")
      (node (ref "D3") (pin "A") (pinfunction "A_A") (pintype "passive"))
      (node (ref "R15") (pin "1") (pinfunction "1_1") (pintype "passive"))
    )
    (net (code "27") (name "Net-(D3-PadC)") (class "Default")
      (node (ref "D3") (pin "C") (pinfunction "C_C") (pintype "passive"))
      (node (ref "JP5") (pin "2") (pinfunction "2_2") (pintype "passive"))
    )
    (net (code "28") (name "Net-(D4-PadA)") (class "Default")
      (node (ref "D4") (pin "A") (pinfunction "A_A") (pintype "passive"))
      (node (ref "R9") (pin "1") (pinfunction "1_1") (pintype "passive"))
    )
    (net (code "29") (name "Net-(D4-PadC)") (class "Default")
      (node (ref "D4") (pin "C") (pinfunction "C_C") (pintype "passive"))
      (node (ref "JP6") (pin "2") (pinfunction "2_2") (pintype "passive"))
    )
    (net (code "30") (name "Net-(L5-1)") (class "Default")
      (node (ref "C15") (pin "1") (pinfunction "1_1") (pintype "passive"))
      (node (ref "C18") (pin "1") (pinfunction "1_1") (pintype "passive"))
      (node (ref "L5") (pin "P$1") (pinfunction "1_P$1") (pintype "passive"))
      (node (ref "R3") (pin "1") (pinfunction "1_1") (pintype "passive"))
    )
    (net (code "31") (name "Net-(L5-2)") (class "Default")
      (node (ref "L5") (pin "P$2") (pinfunction "2_P$2") (pintype "passive"))
      (node (ref "U4") (pin "14") (pinfunction "VCC1_14") (pintype "power_in"))
    )
    (net (code "32") (name "Net-(L6-2)") (class "Default")
      (node (ref "L6") (pin "P$2") (pinfunction "2_P$2") (pintype "passive"))
      (node (ref "L8") (pin "P$1") (pinfunction "1_P$1") (pintype "passive"))
      (node (ref "U4") (pin "10") (pinfunction "RF_OUT/VCC2_10") (pintype "output"))
      (node (ref "U4") (pin "9") (pinfunction "RF_OUT/VCC2_9") (pintype "output"))
    )
    (net (code "33") (name "Net-(L7-1)") (class "Default")
      (node (ref "C25") (pin "2") (pinfunction "2_2") (pintype "passive"))
      (node (ref "L7") (pin "P$1") (pinfunction "1_P$1") (pintype "passive"))
    )
    (net (code "34") (name "Net-(L7-2)") (class "Default")
      (node (ref "L7") (pin "P$2") (pinfunction "2_P$2") (pintype "passive"))
      (node (ref "U4") (pin "3") (pinfunction "RF_IN_3") (pintype "input"))
    )
    (net (code "35") (name "Net-(U1-HOLD)") (class "Default")
      (node (ref "R2") (pin "1") (pinfunction "1_1") (pintype "passive"))
      (node (ref "U1") (pin "7") (pinfunction "HOLD_7") (pintype "bidirectional"))
    )
    (net (code "36") (name "Net-(U1-WP)") (class "Default")
      (node (ref "R11") (pin "1") (pinfunction "1_1") (pintype "passive"))
      (node (ref "U1") (pin "3") (pinfunction "WP_3") (pintype "bidirectional"))
    )
    (net (code "37") (name "Net-(U3-A18VD3)") (class "Default")
      (node (ref "C5") (pin "1") (pinfunction "1_1") (pintype "passive"))
      (node (ref "C6") (pin "1") (pinfunction "1_1") (pintype "passive"))
      (node (ref "L2") (pin "1") (pinfunction "1_1") (pintype "passive"))
      (node (ref "U3") (pin "40") (pinfunction "A18VD3_40") (pintype "power_in"))
    )
    (net (code "38") (name "Net-(U3-A33VD1)") (class "Default")
      (node (ref "C40") (pin "1") (pinfunction "1_1") (pintype "passive"))
      (node (ref "C41") (pin "1") (pinfunction "1_1") (pintype "passive"))
      (node (ref "L15") (pin "1") (pinfunction "1_1") (pintype "passive"))
      (node (ref "U3") (pin "23") (pinfunction "A33VD1_23") (pintype "power_in"))
    )
    (net (code "39") (name "Net-(U3-A33VD2)") (class "Default")
      (node (ref "C7") (pin "1") (pinfunction "1_1") (pintype "passive"))
      (node (ref "C8") (pin "1") (pinfunction "1_1") (pintype "passive"))
      (node (ref "L3") (pin "1") (pinfunction "1_1") (pintype "passive"))
      (node (ref "U3") (pin "36") (pinfunction "A33VD2_36") (pintype "power_in"))
    )
    (net (code "40") (name "Net-(U3-D18VD)") (class "Default")
      (node (ref "C26") (pin "1") (pinfunction "1_1") (pintype "passive"))
      (node (ref "C27") (pin "1") (pinfunction "1_1") (pintype "passive"))
      (node (ref "L9") (pin "1") (pinfunction "1_1") (pintype "passive"))
      (node (ref "U3") (pin "6") (pinfunction "D18VD_6") (pintype "power_in"))
    )
    (net (code "41") (name "Net-(U3-D33VD)") (class "Default")
      (node (ref "C32") (pin "1") (pinfunction "1_1") (pintype "passive"))
      (node (ref "C33") (pin "1") (pinfunction "1_1") (pintype "passive"))
      (node (ref "L10") (pin "1") (pinfunction "1_1") (pintype "passive"))
      (node (ref "R5") (pin "2") (pinfunction "2_2") (pintype "passive"))
      (node (ref "R8") (pin "1") (pinfunction "1_1") (pintype "passive"))
      (node (ref "U3") (pin "9") (pinfunction "D33VD_9") (pintype "power_in"))
    )
    (net (code "42") (name "Net-(U3-FREF)") (class "Default")
      (node (ref "C17") (pin "2") (pinfunction "2_2") (pintype "passive"))
      (node (ref "U3") (pin "38") (pinfunction "FREF_38") (pintype "bidirectional"))
    )
    (net (code "43") (name "Net-(U3-FREFVD)") (class "Default")
      (node (ref "C10") (pin "1") (pinfunction "1_1") (pintype "passive"))
      (node (ref "C9") (pin "1") (pinfunction "1_1") (pintype "passive"))
      (node (ref "U3") (pin "37") (pinfunction "FREFVD_37") (pintype "bidirectional"))
      (node (ref "X1") (pin "4") (pinfunction "VCC_4") (pintype "bidirectional"))
    )
    (net (code "44") (name "Net-(U3-RBIAS)") (class "Default")
      (node (ref "R4") (pin "1") (pinfunction "1_1") (pintype "passive"))
      (node (ref "U3") (pin "41") (pinfunction "RBIAS_41") (pintype "bidirectional"))
    )
    (net (code "45") (name "Net-(U3-TXOUT)") (class "Default")
      (node (ref "C24") (pin "1") (pinfunction "1_1") (pintype "passive"))
      (node (ref "U3") (pin "34") (pinfunction "TXOUT_34") (pintype "bidirectional"))
    )
    (net (code "46") (name "Net-(U4-PD)") (class "Default")
      (node (ref "C43") (pin "2") (pinfunction "2_2") (pintype "passive"))
      (node (ref "C44") (pin "1") (pinfunction "1_1") (pintype "passive"))
      (node (ref "R14") (pin "2") (pinfunction "2_2") (pintype "passive"))
      (node (ref "R17") (pin "2") (pinfunction "2_2") (pintype "passive"))
      (node (ref "U4") (pin "6") (pinfunction "PD_6") (pintype "input"))
    )
    (net (code "47") (name "Net-(U5-J1)") (class "Default")
      (node (ref "C37") (pin "2") (pinfunction "2_2") (pintype "passive"))
      (node (ref "U5") (pin "5") (pinfunction "J1_5") (pintype "bidirectional"))
    )
    (net (code "48") (name "Net-(U5-J2)") (class "Default")
      (node (ref "C30") (pin "1") (pinfunction "1_1") (pintype "passive"))
      (node (ref "U5") (pin "3") (pinfunction "J2_3") (pintype "bidirectional"))
    )
    (net (code "49") (name "Net-(U5-J3)") (class "Default")
      (node (ref "C31") (pin "1") (pinfunction "1_1") (pintype "passive"))
      (node (ref "U5") (pin "1") (pinfunction "J3_1") (pintype "bidirectional"))
    )
    (net (code "50") (name "Net-(X1-OUT)") (class "Default")
      (node (ref "C17") (pin "1") (pinfunction "1_1") (pintype "passive"))
      (node (ref "X1") (pin "3") (pinfunction "OUT_3") (pintype "bidirectional"))
    )
    (net (code "51") (name "PA_PD") (class "Default")
      (node (ref "R17") (pin "1") (pinfunction "1_1") (pintype "passive"))
      (node (ref "U3") (pin "7") (pinfunction "GPIO7_7") (pintype "bidirectional"))
    )
    (net (code "52") (name "RESETB") (class "Default")
      (node (ref "J2") (pin "7") (pinfunction "GPIO2_7") (pintype "bidirectional"))
      (node (ref "R8") (pin "2") (pinfunction "2_2") (pintype "passive"))
      (node (ref "U3") (pin "1") (pinfunction "RESETB_1") (pintype "bidirectional"))
    )
    (net (code "53") (name "RFG8") (class "Default")
      (node (ref "C22") (pin "2") (pinfunction "2_2") (pintype "passive"))
      (node (ref "K1") (pin "4") (pinfunction "DRAIN_2_4") (pintype "bidirectional"))
      (node (ref "R7") (pin "1") (pinfunction "1_1") (pintype "passive"))
      (node (ref "U4") (pin "12") (pinfunction "G8_12") (pintype "input"))
    )
    (net (code "54") (name "RF_PWR_EN") (class "Default")
      (node (ref "J2") (pin "9") (pinfunction "GPIO0_9") (pintype "bidirectional"))
      (node (ref "R16") (pin "2") (pinfunction "2_2") (pintype "passive"))
      (node (ref "U8") (pin "3") (pinfunction "EN_3") (pintype "input"))
    )
    (net (code "55") (name "RF_RX") (class "Default")
      (node (ref "C29") (pin "P$2") (pinfunction "2_P$2") (pintype "passive"))
      (node (ref "C30") (pin "2") (pinfunction "2_2") (pintype "passive"))
      (node (ref "L12") (pin "P$2") (pinfunction "2_P$2") (pintype "passive"))
    )
    (net (code "56") (name "RF_TX") (class "Default")
      (node (ref "C28") (pin "2") (pinfunction "2_2") (pintype "passive"))
      (node (ref "C31") (pin "2") (pinfunction "2_2") (pintype "passive"))
      (node (ref "L8") (pin "P$2") (pinfunction "2_P$2") (pintype "passive"))
    )
    (net (code "57") (name "RXSW") (class "Default")
      (node (ref "C36") (pin "1") (pinfunction "1_1") (pintype "passive"))
      (node (ref "R13") (pin "2") (pinfunction "2_2") (pintype "passive"))
      (node (ref "U3") (pin "22") (pinfunction "RXSW_22") (pintype "bidirectional"))
      (node (ref "U5") (pin "6") (pinfunction "V2_6") (pintype "power_in"))
    )
    (net (code "58") (name "SCLK") (class "Default")
      (node (ref "J2") (pin "18") (pinfunction "SCK_18") (pintype "bidirectional"))
      (node (ref "U3") (pin "3") (pinfunction "SCLK_3") (pintype "bidirectional"))
    )
    (net (code "59") (name "TXSW") (class "Default")
      (node (ref "C42") (pin "1") (pinfunction "1_1") (pintype "passive"))
      (node (ref "R12") (pin "2") (pinfunction "2_2") (pintype "passive"))
      (node (ref "U3") (pin "21") (pinfunction "TXSW_21") (pintype "bidirectional"))
      (node (ref "U5") (pin "4") (pinfunction "V1_4") (pintype "power_in"))
    )
    (net (code "60") (name "VDD") (class "Default")
      (node (ref "C3") (pin "1") (pinfunction "1_1") (pintype "passive"))
      (node (ref "C46") (pin "1") (pinfunction "1_1") (pintype "passive"))
      (node (ref "L1") (pin "2") (pinfunction "2_2") (pintype "passive"))
      (node (ref "L10") (pin "2") (pinfunction "2_2") (pintype "passive"))
      (node (ref "L15") (pin "2") (pinfunction "2_2") (pintype "passive"))
      (node (ref "L3") (pin "2") (pinfunction "2_2") (pintype "passive"))
      (node (ref "R15") (pin "2") (pinfunction "2_2") (pintype "passive"))
      (node (ref "TP1") (pin "P$1") (pinfunction "1_P$1") (pintype "bidirectional"))
      (node (ref "U2") (pin "1") (pinfunction "IN_1") (pintype "input"))
      (node (ref "U2") (pin "3") (pinfunction "EN_3") (pintype "input"))
      (node (ref "U7") (pin "5") (pinfunction "OUT_5") (pintype "passive"))
    )
    (net (code "61") (name "VDDA") (class "Default")
      (node (ref "C14") (pin "1") (pinfunction "1_1") (pintype "passive"))
      (node (ref "C16") (pin "1") (pinfunction "1_1") (pintype "passive"))
      (node (ref "C19") (pin "1") (pinfunction "1_1") (pintype "passive"))
      (node (ref "C47") (pin "1") (pinfunction "1_1") (pintype "passive"))
      (node (ref "L6") (pin "P$1") (pinfunction "1_P$1") (pintype "passive"))
      (node (ref "R3") (pin "2") (pinfunction "2_2") (pintype "passive"))
      (node (ref "R9") (pin "2") (pinfunction "2_2") (pintype "passive"))
      (node (ref "TP2") (pin "P$1") (pinfunction "1_P$1") (pintype "bidirectional"))
      (node (ref "U6") (pin "1") (pinfunction "IN_1") (pintype "input"))
      (node (ref "U6") (pin "3") (pinfunction "EN_3") (pintype "input"))
      (node (ref "U8") (pin "5") (pinfunction "OUT_5") (pintype "passive"))
    )
    (net (code "62") (name "VIN") (class "Default")
      (node (ref "C1") (pin "1") (pinfunction "1_1") (pintype "passive"))
      (node (ref "C48") (pin "1") (pinfunction "1_1") (pintype "passive"))
      (node (ref "D5") (pin "C") (pinfunction "C_C") (pintype "passive"))
      (node (ref "Q1") (pin "2") (pinfunction "S_2") (pintype "bidirectional"))
      (node (ref "U7") (pin "1") (pinfunction "IN_1") (pintype "input"))
      (node (ref "U8") (pin "1") (pinfunction "IN_1") (pintype "input"))
    )
    (net (code "63") (name "VREF1") (class "Default")
      (node (ref "C20") (pin "2") (pinfunction "2_2") (pintype "passive"))
      (node (ref "C21") (pin "2") (pinfunction "2_2") (pintype "passive"))
      (node (ref "C23") (pin "1") (pinfunction "1_1") (pintype "passive"))
      (node (ref "K1") (pin "3") (pinfunction "DRAIN_1_3") (pintype "bidirectional"))
      (node (ref "TP4") (pin "P$1") (pinfunction "1_P$1") (pintype "bidirectional"))
      (node (ref "U4") (pin "13") (pinfunction "G16_13") (pintype "input"))
      (node (ref "U4") (pin "16") (pinfunction "VBIAS_16") (pintype "power_in"))
      (node (ref "U6") (pin "5") (pinfunction "OUT_5") (pintype "passive"))
    )
    (net (code "64") (name "V_BATT") (class "Default")
      (node (ref "J2") (pin "12") (pinfunction "VBAT_12") (pintype "bidirectional"))
      (node (ref "Q1") (pin "3") (pinfunction "D_3") (pintype "bidirectional"))
    )
    (net (code "65") (name "V_USB") (class "Default")
      (node (ref "D5") (pin "A") (pinfunction "A_A") (pintype "passive"))
      (node (ref "J2") (pin "10") (pinfunction "VUSB_10") (pintype "bidirectional"))
      (node (ref "Q1") (pin "1") (pinfunction "G_1") (pintype "bidirectional"))
      (node (ref "R10") (pin "2") (pinfunction "2_2") (pintype "passive"))
    )
    (net (code "66") (name "unconnected-(J2-3V3-Pad27)") (class "Default")
      (node (ref "J2") (pin "27") (pinfunction "3V3_27") (pintype "bidirectional"))
    )
    (net (code "67") (name "unconnected-(J2-A0-Pad24)") (class "Default")
      (node (ref "J2") (pin "24") (pinfunction "A0_24") (pintype "bidirectional"))
    )
    (net (code "68") (name "unconnected-(J2-A1-Pad23)") (class "Default")
      (node (ref "J2") (pin "23") (pinfunction "A1_23") (pintype "bidirectional"))
    )
    (net (code "69") (name "unconnected-(J2-A2-Pad22)") (class "Default")
      (node (ref "J2") (pin "22") (pinfunction "A2_22") (pintype "bidirectional"))
    )
    (net (code "70") (name "unconnected-(J2-A3-Pad21)") (class "Default")
      (node (ref "J2") (pin "21") (pinfunction "A3_21") (pintype "bidirectional"))
    )
    (net (code "71") (name "unconnected-(J2-A4-Pad20)") (class "Default")
      (node (ref "J2") (pin "20") (pinfunction "A4_20") (pintype "bidirectional"))
    )
    (net (code "72") (name "unconnected-(J2-FREE-Pad13)") (class "Default")
      (node (ref "J2") (pin "13") (pinfunction "FREE_13") (pintype "bidirectional"))
    )
    (net (code "73") (name "unconnected-(J2-NC-Pad26)") (class "Default")
      (node (ref "J2") (pin "26") (pinfunction "NC_26") (pintype "bidirectional"))
    )
    (net (code "74") (name "unconnected-(J2-RX-Pad15)") (class "Default")
      (node (ref "J2") (pin "15") (pinfunction "RX_15") (pintype "bidirectional"))
    )
    (net (code "75") (name "unconnected-(J2-SCL-Pad2)") (class "Default")
      (node (ref "J2") (pin "2") (pinfunction "SCL_2") (pintype "bidirectional"))
    )
    (net (code "76") (name "unconnected-(J2-SDA-Pad1)") (class "Default")
      (node (ref "J2") (pin "1") (pinfunction "SDA_1") (pintype "bidirectional"))
    )
    (net (code "77") (name "unconnected-(J2-TX-Pad14)") (class "Default")
      (node (ref "J2") (pin "14") (pinfunction "TX_14") (pintype "bidirectional"))
    )
    (net (code "78") (name "unconnected-(J2-~{EN}-Pad11)") (class "Default")
      (node (ref "J2") (pin "11") (pinfunction "~{EN}_11") (pintype "bidirectional"))
    )
    (net (code "79") (name "unconnected-(J2-~{RESET}-Pad28)") (class "Default")
      (node (ref "J2") (pin "28") (pinfunction "~{RESET}_28") (pintype "bidirectional"))
    )
    (net (code "80") (name "unconnected-(U2-NC-Pad4)") (class "Default")
      (node (ref "U2") (pin "4") (pinfunction "NC_4") (pintype "no_connect"))
    )
    (net (code "81") (name "unconnected-(U3-GPIO0-Pad19)") (class "Default")
      (node (ref "U3") (pin "19") (pinfunction "GPIO0_19") (pintype "bidirectional"))
    )
    (net (code "82") (name "unconnected-(U3-GPIO1-Pad18)") (class "Default")
      (node (ref "U3") (pin "18") (pinfunction "GPIO1_18") (pintype "bidirectional"))
    )
    (net (code "83") (name "unconnected-(U3-GPIO2-Pad17)") (class "Default")
      (node (ref "U3") (pin "17") (pinfunction "GPIO2_17") (pintype "bidirectional"))
    )
    (net (code "84") (name "unconnected-(U3-GPIO3-Pad16)") (class "Default")
      (node (ref "U3") (pin "16") (pinfunction "GPIO3_16") (pintype "bidirectional"))
    )
    (net (code "85") (name "unconnected-(U3-GPIO4-Pad11)") (class "Default")
      (node (ref "U3") (pin "11") (pinfunction "GPIO4_11") (pintype "bidirectional"))
    )
    (net (code "86") (name "unconnected-(U3-GPIO5-Pad10)") (class "Default")
      (node (ref "U3") (pin "10") (pinfunction "GPIO5_10") (pintype "bidirectional"))
    )
    (net (code "87") (name "unconnected-(U3-GPIO6-Pad8)") (class "Default")
      (node (ref "U3") (pin "8") (pinfunction "GPIO6_8") (pintype "bidirectional"))
    )
    (net (code "88") (name "unconnected-(U3-NC-Pad42)") (class "Default")
      (node (ref "U3") (pin "42") (pinfunction "NC_42") (pintype "no_connect"))
    )
    (net (code "89") (name "unconnected-(U3-NC-Pad43)") (class "Default")
      (node (ref "U3") (pin "43") (pinfunction "NC_43") (pintype "no_connect"))
    )
    (net (code "90") (name "unconnected-(U3-NC-Pad44)") (class "Default")
      (node (ref "U3") (pin "44") (pinfunction "NC_44") (pintype "no_connect"))
    )
    (net (code "91") (name "unconnected-(U3-NC-Pad45)") (class "Default")
      (node (ref "U3") (pin "45") (pinfunction "NC_45") (pintype "no_connect"))
    )
    (net (code "92") (name "unconnected-(U4-NC-Pad1)") (class "Default")
      (node (ref "U4") (pin "1") (pinfunction "NC_1") (pintype "no_connect"))
    )
    (net (code "93") (name "unconnected-(U4-NC-Pad4)") (class "Default")
      (node (ref "U4") (pin "4") (pinfunction "NC_4") (pintype "no_connect"))
    )
    (net (code "94") (name "unconnected-(U4-NC-Pad5)") (class "Default")
      (node (ref "U4") (pin "5") (pinfunction "NC_5") (pintype "no_connect"))
    )
    (net (code "95") (name "unconnected-(U4-NC-Pad7)") (class "Default")
      (node (ref "U4") (pin "7") (pinfunction "NC_7") (pintype "no_connect"))
    )
    (net (code "96") (name "unconnected-(U4-NC-Pad8)") (class "Default")
      (node (ref "U4") (pin "8") (pinfunction "NC_8") (pintype "no_connect"))
    )
    (net (code "97") (name "unconnected-(U4-NC-Pad11)") (class "Default")
      (node (ref "U4") (pin "11") (pinfunction "NC_11") (pintype "no_connect"))
    )
    (net (code "98") (name "unconnected-(U4-NC-Pad15)") (class "Default")
      (node (ref "U4") (pin "15") (pinfunction "NC_15") (pintype "no_connect"))
    )
    (net (code "99") (name "unconnected-(U6-NC-Pad4)") (class "Default")
      (node (ref "U6") (pin "4") (pinfunction "NC_4") (pintype "no_connect"))
    )
    (net (code "100") (name "unconnected-(U7-NC-Pad4)") (class "Default")
      (node (ref "U7") (pin "4") (pinfunction "NC_4") (pintype "no_connect"))
    )
    (net (code "101") (name "unconnected-(U8-NC-Pad4)") (class "Default")
      (node (ref "U8") (pin "4") (pinfunction "NC_4") (pintype "no_connect"))
    )
  )
)
